# QCopterFC_CAM_Sch.net
KiCad netlist of a schematic drawn in Altium Designer
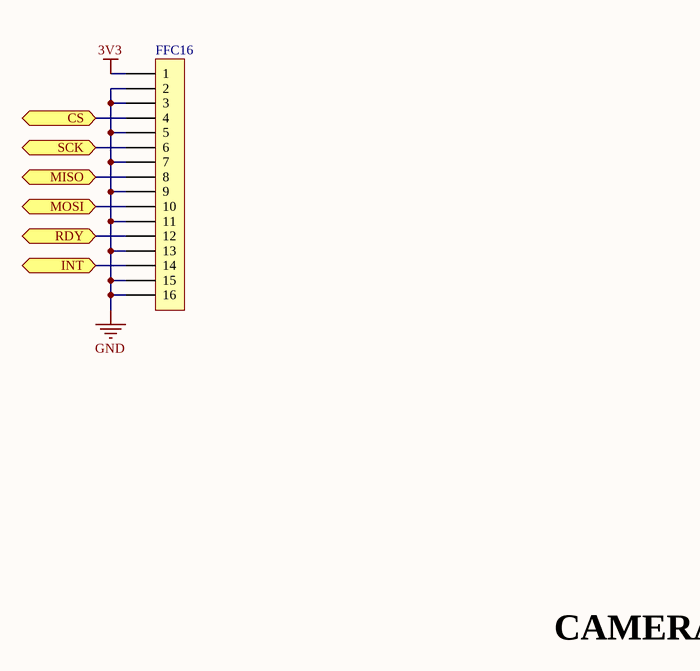
[diagram p0: QCopterFC_CAM_Sch.SchDoc]

(export (version "E")
  (design (tool "Eeschema 10.0.6"))
  (components
    (comp (ref "FFC16")
      (value "FFC_0.5_16")
      (footprint "PCB_Connector:FFC_0.5_16")
      (description "FFC")
      (libsource (lib "SCH_Connector") (part "FFC_0.5_16"))
    )
  )
  (nets
    (net (code "1") (name "/CS") (class "Default")
      (node (ref "FFC16") (pin "4") (pinfunction "4_4") (pintype "passive"))
    )
    (net (code "2") (name "/INT") (class "Default")
      (node (ref "FFC16") (pin "14") (pinfunction "14_14") (pintype "passive"))
    )
    (net (code "3") (name "/MISO") (class "Default")
      (node (ref "FFC16") (pin "8") (pinfunction "8_8") (pintype "passive"))
    )
    (net (code "4") (name "/MOSI") (class "Default")
      (node (ref "FFC16") (pin "10") (pinfunction "10_10") (pintype "passive"))
    )
    (net (code "5") (name "/RDY") (class "Default")
      (node (ref "FFC16") (pin "12") (pinfunction "12_12") (pintype "passive"))
    )
    (net (code "6") (name "/SCK") (class "Default")
      (node (ref "FFC16") (pin "6") (pinfunction "6_6") (pintype "passive"))
    )
    (net (code "7") (name "3V3") (class "Default")
      (node (ref "FFC16") (pin "1") (pinfunction "1_1") (pintype "passive"))
    )
    (net (code "8") (name "GND") (class "Default")
      (node (ref "FFC16") (pin "11") (pinfunction "11_11") (pintype "passive"))
      (node (ref "FFC16") (pin "13") (pinfunction "13_13") (pintype "passive"))
      (node (ref "FFC16") (pin "15") (pinfunction "15_15") (pintype "passive"))
      (node (ref "FFC16") (pin "16") (pinfunction "16_16") (pintype "passive"))
      (node (ref "FFC16") (pin "2") (pinfunction "2_2") (pintype "passive"))
      (node (ref "FFC16") (pin "3") (pinfunction "3_3") (pintype "passive"))
      (node (ref "FFC16") (pin "5") (pinfunction "5_5") (pintype "passive"))
      (node (ref "FFC16") (pin "7") (pinfunction "7_7") (pintype "passive"))
      (node (ref "FFC16") (pin "9") (pinfunction "9_9") (pintype "passive"))
    )
  )
)
